# USBDM_Kinetis.net
KiCad netlist of a schematic drawn in Altium Designer
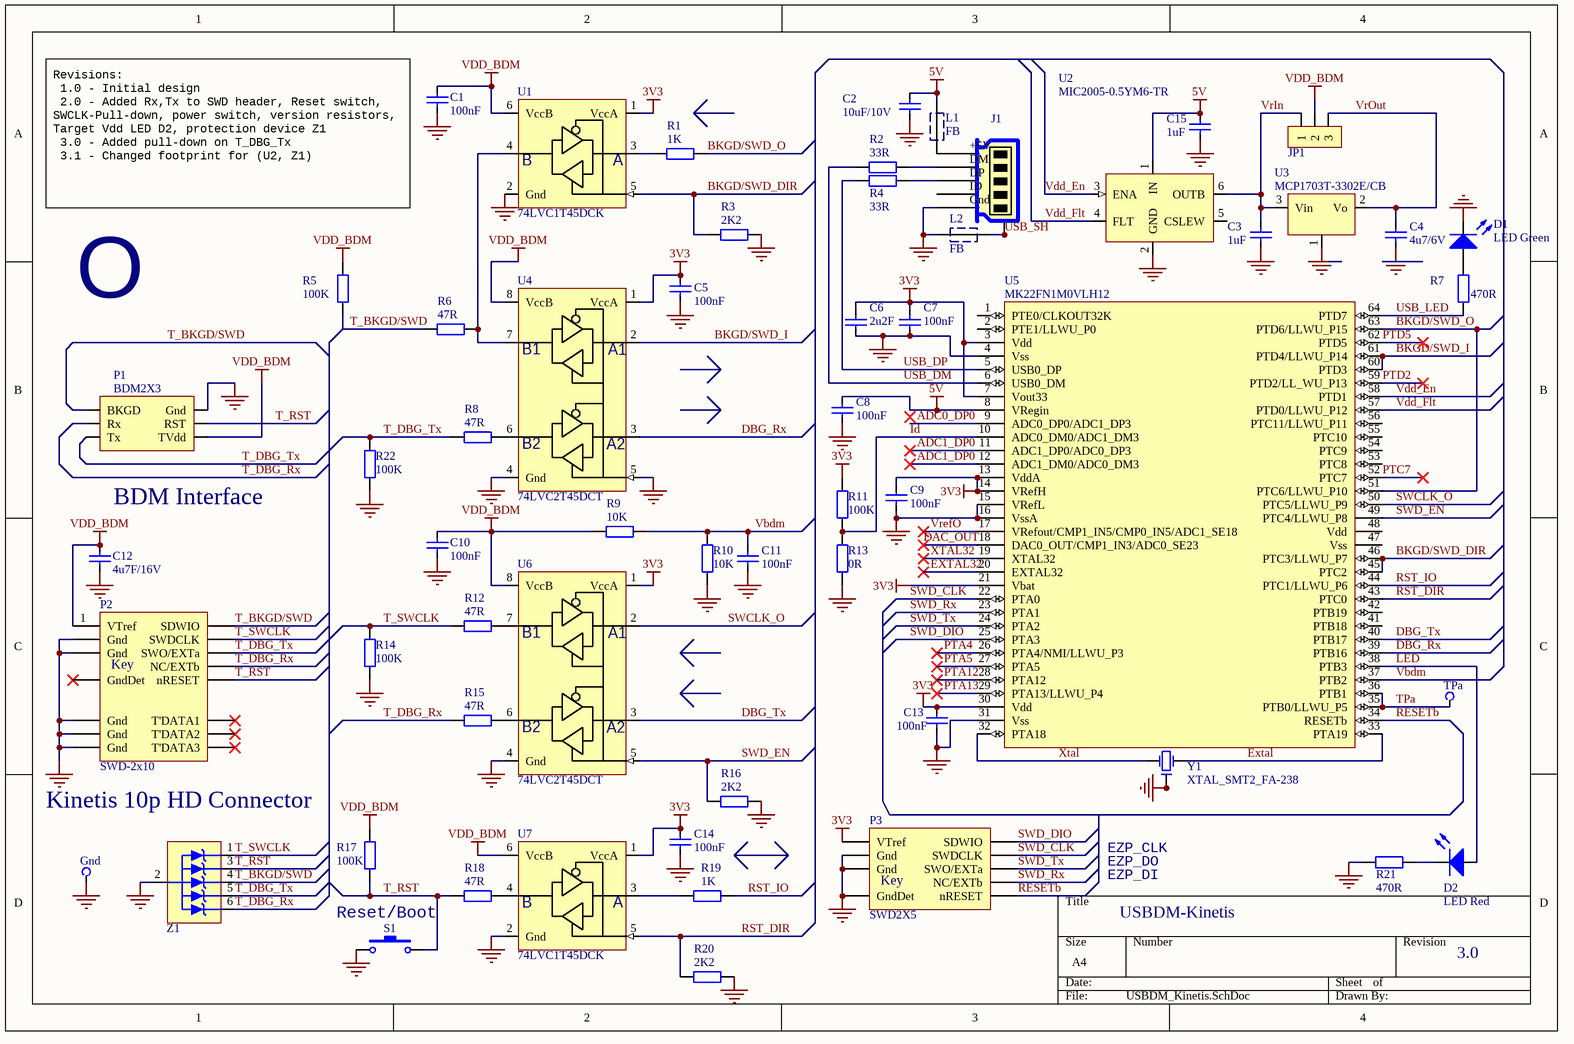
[diagram p0: USBDM_Kinetis.SchDoc]

(export (version "E")
  (design (tool "Eeschema 10.0.6"))
  (components
    (comp (ref "C1")
      (value "100nF")
      (footprint "CCNP1608-0603")
      (description "Capacitor")
      (fields
        (field (name "MANUFACTURER") "Generic Components")
        (field (name "PUBLISHER") "Altium Hobart Technology Centre")
      )
      (libsource (lib "MyLibrary") (part "Cap_CCNP_0603"))
    )
    (comp (ref "C2")
      (value "10uF/10V")
      (footprint "CCNP2012-0805")
      (description "Capacitor SMT 0805")
      (fields
        (field (name "MANUFACTURER") "Generic Components")
        (field (name "PUBLISHER") "Altium Hobart Technology Centre")
      )
      (libsource (lib "MyLibrary") (part "Cap_CCNP_0805"))
    )
    (comp (ref "C3")
      (value "1uF")
      (footprint "CCNP1608-0603")
      (description "Capacitor SMT")
      (fields
        (field (name "MANUFACTURER") "Generic Components")
        (field (name "PUBLISHER") "Altium Hobart Technology Centre")
      )
      (libsource (lib "MyLibrary") (part "Cap"))
    )
    (comp (ref "C4")
      (value "4u7/6V")
      (footprint "CCNP1608-0603")
      (description "Capacitor SMT 0603")
      (fields
        (field (name "MANUFACTURER") "Generic Components")
        (field (name "PUBLISHER") "Altium Hobart Technology Centre")
      )
      (libsource (lib "MyLibrary") (part "Cap_CCNP_0603"))
    )
    (comp (ref "C5")
      (value "100nF")
      (footprint "CCNP1608-0603")
      (description "Capacitor")
      (fields
        (field (name "MANUFACTURER") "Generic Components")
        (field (name "PUBLISHER") "Altium Hobart Technology Centre")
      )
      (libsource (lib "MyLibrary") (part "Cap_CCNP_0603"))
    )
    (comp (ref "C6")
      (value "2u2F")
      (footprint "CCNP1608-0603")
      (description "Capacitor SMT 0603")
      (fields
        (field (name "MANUFACTURER") "Generic Components")
        (field (name "PUBLISHER") "Altium Hobart Technology Centre")
      )
      (libsource (lib "MyLibrary") (part "Cap_CCNP_0603"))
    )
    (comp (ref "C7")
      (value "100nF")
      (footprint "CCNP1608-0603")
      (description "Capacitor")
      (fields
        (field (name "MANUFACTURER") "Generic Components")
        (field (name "PUBLISHER") "Altium Hobart Technology Centre")
      )
      (libsource (lib "MyLibrary") (part "Cap_CCNP_0603"))
    )
    (comp (ref "C8")
      (value "100nF")
      (footprint "CCNP1608-0603")
      (description "Capacitor")
      (fields
        (field (name "MANUFACTURER") "Generic Components")
        (field (name "PUBLISHER") "Altium Hobart Technology Centre")
      )
      (libsource (lib "MyLibrary") (part "Cap_CCNP_0603"))
    )
    (comp (ref "C9")
      (value "100nF")
      (footprint "CCNP1608-0603")
      (description "Capacitor")
      (fields
        (field (name "MANUFACTURER") "Generic Components")
        (field (name "PUBLISHER") "Altium Hobart Technology Centre")
      )
      (libsource (lib "MyLibrary") (part "Cap_CCNP_0603"))
    )
    (comp (ref "C10")
      (value "100nF")
      (footprint "CCNP1608-0603")
      (description "Capacitor")
      (fields
        (field (name "MANUFACTURER") "Generic Components")
        (field (name "PUBLISHER") "Altium Hobart Technology Centre")
      )
      (libsource (lib "MyLibrary") (part "Cap_CCNP_0603"))
    )
    (comp (ref "C11")
      (value "100nF")
      (footprint "CCNP1608-0603")
      (description "Capacitor")
      (fields
        (field (name "MANUFACTURER") "Generic Components")
        (field (name "PUBLISHER") "Altium Hobart Technology Centre")
      )
      (libsource (lib "MyLibrary") (part "Cap_CCNP_0603"))
    )
    (comp (ref "C12")
      (value "4u7F/16V")
      (footprint "CCNP2012-0805")
      (description "Capacitor SMT 0805")
      (fields
        (field (name "MANUFACTURER") "Generic Components")
        (field (name "PUBLISHER") "Altium Hobart Technology Centre")
      )
      (libsource (lib "MyLibrary") (part "Cap_CCNP_0805"))
    )
    (comp (ref "C13")
      (value "100nF")
      (footprint "CCNP1608-0603")
      (description "Capacitor")
      (fields
        (field (name "MANUFACTURER") "Generic Components")
        (field (name "PUBLISHER") "Altium Hobart Technology Centre")
      )
      (libsource (lib "MyLibrary") (part "Cap_CCNP_0603"))
    )
    (comp (ref "C14")
      (value "100nF")
      (footprint "CCNP1608-0603")
      (description "Capacitor")
      (fields
        (field (name "MANUFACTURER") "Generic Components")
        (field (name "PUBLISHER") "Altium Hobart Technology Centre")
      )
      (libsource (lib "MyLibrary") (part "Cap_CCNP_0603"))
    )
    (comp (ref "C15")
      (value "1uF")
      (footprint "CCNP1608-0603")
      (description "Capacitor SMT")
      (fields
        (field (name "MANUFACTURER") "Generic Components")
        (field (name "PUBLISHER") "Altium Hobart Technology Centre")
      )
      (libsource (lib "MyLibrary") (part "Cap"))
    )
    (comp (ref "D1")
      (value "LED Green")
      (footprint "CD1608-0603")
      (description "LED (Red 0603)")
      (fields (field (name "MANUFACTURER") "Generic Components") (field (name "PUBLISHER") "Altium Limited"))
      (libsource (lib "MySchLib") (part "LED SMT,Red-0603"))
    )
    (comp (ref "D2")
      (value "LED Red")
      (footprint "CD1608-0603")
      (description "LED (Red 0603)")
      (fields (field (name "MANUFACTURER") "Generic Components") (field (name "PUBLISHER") "Altium Limited"))
      (libsource (lib "MySchLib") (part "LED SMT,Red-0603"))
    )
    (comp (ref "Gnd")
      (value "TP")
      (footprint "PCBPIN - 0.9mm")
      (description "Test Point")
      (libsource (lib "MyLibrary") (part "TP"))
    )
    (comp (ref "J1")
      (value "USB_MICRO_B_CONNECTOR")
      (footprint "MOLEX - 47346-0001")
      (description "USB Micro-B Connector")
      (libsource (lib "MySchLib") (part "USB_MICRO_B_CONNECTOR"))
    )
    (comp (ref "JP1")
      (value "Header 1x3 2mm")
      (footprint "Header 1x3 (2mm)")
      (description "Header, 1x3, 2mm")
      (fields (field (name "MANUFACTURER") "Generic Components") (field (name "PUBLISHER") "Altium Limited"))
      (libsource (lib "MySchLib") (part "Header 1x3 2mm"))
    )
    (comp (ref "L1")
      (value "FB")
      (footprint "CR2012-0805")
      (description "Ferrite Bead (0805) 0.045OHM, 2A")
      (libsource (lib "MySchLib") (part "Ferrite Bead 0805"))
    )
    (comp (ref "L2")
      (value "FB")
      (footprint "CR2012-0805")
      (description "Ferrite Bead (0805) 0.045OHM, 2A")
      (libsource (lib "MySchLib") (part "Ferrite Bead 0805"))
    )
    (comp (ref "Logo1")
      (value "OSHW Logo")
      (footprint "OSHW")
      (libsource (lib "MySchLib") (part "OSHW Logo"))
    )
    (comp (ref "P1") (value "BDM2X3") (footprint "BDM") (libsource (lib "MyLibrary") (part "BDM2X3")))
    (comp (ref "P2")
      (value "SWD-2x10")
      (footprint "SWD-2x10 - reduced")
      (description "SWD Connector 2x10-Pin")
      (fields (field (name "PUBLISHER") "Altium Limited"))
      (libsource (lib "MySchLib") (part "SWD2X10-Reduced"))
    )
    (comp (ref "P3")
      (value "SWD2X5")
      (footprint "SWD-2x5")
      (description "SWD Connector 2x5-Pin")
      (fields (field (name "PUBLISHER") "Altium Limited"))
      (libsource (lib "MySchLib") (part "SWD2X5"))
    )
    (comp (ref "R1")
      (value "1K")
      (footprint "CR1608-0603")
      (description "Resistor SMT")
      (fields
        (field (name "MANUFACTURER") "Generic Components")
        (field (name "PUBLISHER") "Altium Hobart Technology Centre")
      )
      (libsource (lib "") (part "Res_CR0603_3"))
    )
    (comp (ref "R2")
      (value "33R")
      (footprint "CR1608-0603")
      (description "Resistor")
      (fields
        (field (name "MANUFACTURER") "Generic Components")
        (field (name "PUBLISHER") "Altium Hobart Technology Centre")
      )
      (libsource (lib "MyLibrary") (part "Res_CR0603"))
    )
    (comp (ref "R3")
      (value "2K2")
      (footprint "CR1608-0603")
      (description "Resistor SMT")
      (fields
        (field (name "MANUFACTURER") "Generic Components")
        (field (name "PUBLISHER") "Altium Hobart Technology Centre")
      )
      (libsource (lib "") (part "Res_CR0603_5"))
    )
    (comp (ref "R4")
      (value "33R")
      (footprint "CR1608-0603")
      (description "Resistor")
      (fields
        (field (name "MANUFACTURER") "Generic Components")
        (field (name "PUBLISHER") "Altium Hobart Technology Centre")
      )
      (libsource (lib "MyLibrary") (part "Res_CR0603"))
    )
    (comp (ref "R5")
      (value "100K")
      (footprint "CR1608-0603")
      (description "Resistor SMT")
      (fields
        (field (name "MANUFACTURER") "Generic Components")
        (field (name "PUBLISHER") "Altium Hobart Technology Centre")
      )
      (libsource (lib "") (part "Res_CR0603_4"))
    )
    (comp (ref "R6")
      (value "47R")
      (footprint "CR1608-0603")
      (description "Resistor SMT")
      (fields
        (field (name "MANUFACTURER") "Generic Components")
        (field (name "PUBLISHER") "Altium Hobart Technology Centre")
      )
      (libsource (lib "") (part "Res_CR0603_2"))
    )
    (comp (ref "R7")
      (value "470R")
      (footprint "CR1608-0603")
      (description "Resistor SMT")
      (fields
        (field (name "MANUFACTURER") "Generic Components")
        (field (name "PUBLISHER") "Altium Hobart Technology Centre")
      )
      (libsource (lib "") (part "Res_CR0603_3"))
    )
    (comp (ref "R8")
      (value "47R")
      (footprint "CR1608-0603")
      (description "Resistor SMT")
      (fields
        (field (name "MANUFACTURER") "Generic Components")
        (field (name "PUBLISHER") "Altium Hobart Technology Centre")
      )
      (libsource (lib "") (part "Res_CR0603_2"))
    )
    (comp (ref "R9")
      (value "10K")
      (footprint "CR1608-0603")
      (description "Resistor SMT")
      (fields
        (field (name "MANUFACTURER") "Generic Components")
        (field (name "PUBLISHER") "Altium Hobart Technology Centre")
      )
      (libsource (lib "") (part "Res_CR0603_2"))
    )
    (comp (ref "R10")
      (value "10K")
      (footprint "CR1608-0603")
      (description "Resistor SMT")
      (fields
        (field (name "MANUFACTURER") "Generic Components")
        (field (name "PUBLISHER") "Altium Hobart Technology Centre")
      )
      (libsource (lib "") (part "Res_CR0603_3"))
    )
    (comp (ref "R11")
      (value "100K")
      (footprint "CR1608-0603")
      (description "Resistor")
      (fields
        (field (name "MANUFACTURER") "Generic Components")
        (field (name "PUBLISHER") "Altium Hobart Technology Centre")
      )
      (libsource (lib "") (part "Res_CR0603_6"))
    )
    (comp (ref "R12")
      (value "47R")
      (footprint "CR1608-0603")
      (description "Resistor SMT")
      (fields
        (field (name "MANUFACTURER") "Generic Components")
        (field (name "PUBLISHER") "Altium Hobart Technology Centre")
      )
      (libsource (lib "") (part "Res_CR0603_2"))
    )
    (comp (ref "R13")
      (value "0R")
      (footprint "CR1608-0603")
      (description "Resistor")
      (fields
        (field (name "MANUFACTURER") "Generic Components")
        (field (name "PUBLISHER") "Altium Hobart Technology Centre")
      )
      (libsource (lib "") (part "Res_CR0603_6"))
    )
    (comp (ref "R14")
      (value "100K")
      (footprint "CR1608-0603")
      (description "Resistor SMT")
      (fields
        (field (name "MANUFACTURER") "Generic Components")
        (field (name "PUBLISHER") "Altium Hobart Technology Centre")
      )
      (libsource (lib "") (part "Res_CR0603_1"))
    )
    (comp (ref "R15")
      (value "47R")
      (footprint "CR1608-0603")
      (description "Resistor SMT")
      (fields
        (field (name "MANUFACTURER") "Generic Components")
        (field (name "PUBLISHER") "Altium Hobart Technology Centre")
      )
      (libsource (lib "") (part "Res_CR0603_2"))
    )
    (comp (ref "R16")
      (value "2K2")
      (footprint "CR1608-0603")
      (description "Resistor SMT")
      (fields
        (field (name "MANUFACTURER") "Generic Components")
        (field (name "PUBLISHER") "Altium Hobart Technology Centre")
      )
      (libsource (lib "") (part "Res_CR0603_7"))
    )
    (comp (ref "R17")
      (value "100K")
      (footprint "CR1608-0603")
      (description "Resistor SMT")
      (fields
        (field (name "MANUFACTURER") "Generic Components")
        (field (name "PUBLISHER") "Altium Hobart Technology Centre")
      )
      (libsource (lib "") (part "Res_CR0603_4"))
    )
    (comp (ref "R18")
      (value "47R")
      (footprint "CR1608-0603")
      (description "Resistor SMT")
      (fields
        (field (name "MANUFACTURER") "Generic Components")
        (field (name "PUBLISHER") "Altium Hobart Technology Centre")
      )
      (libsource (lib "") (part "Res_CR0603_2"))
    )
    (comp (ref "R19")
      (value "1K")
      (footprint "CR1608-0603")
      (description "Resistor SMT")
      (fields
        (field (name "MANUFACTURER") "Generic Components")
        (field (name "PUBLISHER") "Altium Hobart Technology Centre")
      )
      (libsource (lib "") (part "Res_CR0603_2"))
    )
    (comp (ref "R20")
      (value "2K2")
      (footprint "CR1608-0603")
      (description "Resistor SMT")
      (fields
        (field (name "MANUFACTURER") "Generic Components")
        (field (name "PUBLISHER") "Altium Hobart Technology Centre")
      )
      (libsource (lib "") (part "Res_CR0603_5"))
    )
    (comp (ref "R21")
      (value "470R")
      (footprint "CR1608-0603")
      (description "Resistor SMT")
      (fields
        (field (name "MANUFACTURER") "Generic Components")
        (field (name "PUBLISHER") "Altium Hobart Technology Centre")
      )
      (libsource (lib "") (part "Res_CR0603_5"))
    )
    (comp (ref "R22")
      (value "100K")
      (footprint "CR1608-0603")
      (description "Resistor SMT")
      (fields
        (field (name "MANUFACTURER") "Generic Components")
        (field (name "PUBLISHER") "Altium Hobart Technology Centre")
      )
      (libsource (lib "") (part "Res_CR0603_1"))
    )
    (comp (ref "S1")
      (value "SW-PB-SMT-B3U")
      (footprint "SW_SMT_PB2-B3U")
      (description "Switch OMRON B3U series")
      (fields (field (name "MANUFACTURER") "Generic Components") (field (name "PUBLISHER") "Altium Limited"))
      (libsource (lib "MyLibrary") (part "SW-PB-SMT-B3U"))
    )
    (comp (ref "TPa")
      (value "TP")
      (footprint "PCBPIN - 0.9mm")
      (description "Test Point")
      (libsource (lib "MyLibrary") (part "TP"))
    )
    (comp (ref "U1")
      (value "74LVC1T45DCK")
      (footprint "SC70_N")
      (description "Dual voltage bidirection buffer")
      (libsource (lib "MySchLib") (part "74LVC1T45DCK"))
    )
    (comp (ref "U2")
      (value "MIC2005-0.5YM6-TR")
      (footprint "SOT23-6-Power")
      (description "Power Switch")
      (libsource (lib "MySchLib") (part "MIC2005-0.5YM6-TR"))
    )
    (comp (ref "U3")
      (value "MCP1703T-3302E/CB")
      (footprint "SOT23")
      (description "3V3 LDO regulator")
      (libsource (lib "MyLibrary") (part "MCP1703T-3302E/CB"))
    )
    (comp (ref "U4")
      (value "74LVC2T45DCT")
      (footprint "SSOP8_N")
      (description "Dual voltage bidirection buffer")
      (libsource (lib "MySchLib") (part "74LVC2T45DCT"))
    )
    (comp (ref "U5")
      (value "MK22FN1M0VLH12")
      (footprint "TSQFP50P1200X1200-64N")
      (description "Arm Cortex M4F")
      (libsource (lib "MyLibrary") (part "MK22FN1M0VLH12"))
    )
    (comp (ref "U6")
      (value "74LVC2T45DCT")
      (footprint "SSOP8_N")
      (description "Dual voltage bidirection buffer")
      (libsource (lib "MySchLib") (part "74LVC2T45DCT"))
    )
    (comp (ref "U7")
      (value "74LVC1T45DCK")
      (footprint "SC70_N")
      (description "Dual voltage bidirection buffer")
      (libsource (lib "MySchLib") (part "74LVC1T45DCK"))
    )
    (comp (ref "Y1")
      (value "XTAL_SMT2_FA-238")
      (footprint "Crystal_SMT - EPSON-FA-238")
      (description "Crystal (EPSON  Q22FA23800065 FA-238 24 MHZ 12.0PF)")
      (fields
        (field (name "MANUFACTURER") "Generic Components")
        (field (name "PUBLISHER") "Altium Hobart Technology Centre")
      )
      (libsource (lib "MyLibrary") (part "XTAL_SMT2_FA-238"))
    )
    (comp (ref "Z1")
      (value "82402305")
      (footprint "SOT23-6")
      (description "Quintuple Unipolar Protection Device (5V)")
      (libsource (lib "MySchLib") (part "82402305"))
    )
  )
  (nets
    (net (code "1") (name "/ADC0_DP0") (class "Default")
      (node (ref "U5") (pin "9") (pinfunction "ADC0_DP0/ADC1_DP3_9") (pintype "passive"))
    )
    (net (code "2") (name "/ADC1_DP0") (class "Default")
      (node (ref "U5") (pin "11") (pinfunction "ADC1_DP0/ADC0_DP3_11") (pintype "passive"))
      (node (ref "U5") (pin "12") (pinfunction "ADC1_DM0/ADC0_DM3_12") (pintype "passive"))
    )
    (net (code "3") (name "/BKGD{slash}SWD_DIR") (class "Default")
      (node (ref "R3") (pin "1") (pinfunction "1_1") (pintype "passive"))
      (node (ref "U1") (pin "5") (pinfunction "DIR_5") (pintype "input"))
      (node (ref "U5") (pin "45") (pinfunction "PTC2_45") (pintype "bidirectional"))
      (node (ref "U5") (pin "46") (pinfunction "PTC3/LLWU_P7_46") (pintype "bidirectional"))
    )
    (net (code "4") (name "/BKGD{slash}SWD_I") (class "Default")
      (node (ref "U4") (pin "2") (pinfunction "A1_2") (pintype "bidirectional"))
      (node (ref "U5") (pin "60") (pinfunction "PTD3_60") (pintype "bidirectional"))
      (node (ref "U5") (pin "61") (pinfunction "PTD4/LLWU_P14_61") (pintype "bidirectional"))
    )
    (net (code "5") (name "/BKGD{slash}SWD_O") (class "Default")
      (node (ref "R1") (pin "1") (pinfunction "1_1") (pintype "passive"))
      (node (ref "U5") (pin "51") (pinfunction "PTC6/LLWU_P10_51") (pintype "bidirectional"))
      (node (ref "U5") (pin "63") (pinfunction "PTD6/LLWU_P15_63") (pintype "bidirectional"))
    )
    (net (code "6") (name "/DAC_OUT") (class "Default")
      (node (ref "U5") (pin "18") (pinfunction "DAC0_OUT/CMP1_IN3/ADC0_SE23_18") (pintype "passive+no_connect"))
    )
    (net (code "7") (name "/DBG_Rx") (class "Default")
      (node (ref "U4") (pin "3") (pinfunction "A2_3") (pintype "bidirectional"))
      (node (ref "U5") (pin "39") (pinfunction "PTB16_39") (pintype "bidirectional"))
    )
    (net (code "8") (name "/DBG_Tx") (class "Default")
      (node (ref "U5") (pin "40") (pinfunction "PTB17_40") (pintype "bidirectional"))
      (node (ref "U6") (pin "3") (pinfunction "A2_3") (pintype "bidirectional"))
    )
    (net (code "9") (name "/EXTAL32") (class "Default")
      (node (ref "U5") (pin "20") (pinfunction "EXTAL32_20") (pintype "passive+no_connect"))
    )
    (net (code "10") (name "/Extal") (class "Default")
      (node (ref "U5") (pin "33") (pinfunction "PTA19_33") (pintype "bidirectional"))
      (node (ref "Y1") (pin "3") (pinfunction "OSC2_3") (pintype "passive"))
    )
    (net (code "11") (name "/Id") (class "Default")
      (node (ref "R11") (pin "1") (pinfunction "1_1") (pintype "passive"))
      (node (ref "R13") (pin "2") (pinfunction "2_2") (pintype "passive"))
      (node (ref "U5") (pin "10") (pinfunction "ADC0_DM0/ADC1_DM3_10") (pintype "passive"))
    )
    (net (code "12") (name "/LED") (class "Default")
      (node (ref "D2") (pin "A") (pinfunction "A_A") (pintype "passive"))
      (node (ref "U5") (pin "38") (pinfunction "PTB3_38") (pintype "bidirectional"))
    )
    (net (code "13") (name "/PTA4") (class "Default")
      (node (ref "U5") (pin "26") (pinfunction "PTA4/NMI/LLWU_P3_26") (pintype "bidirectional+no_connect"))
    )
    (net (code "14") (name "/PTA5") (class "Default")
      (node (ref "U5") (pin "27") (pinfunction "PTA5_27") (pintype "bidirectional+no_connect"))
    )
    (net (code "15") (name "/PTA12") (class "Default")
      (node (ref "U5") (pin "28") (pinfunction "PTA12_28") (pintype "bidirectional+no_connect"))
    )
    (net (code "16") (name "/PTA13") (class "Default")
      (node (ref "U5") (pin "29") (pinfunction "PTA13/LLWU_P4_29") (pintype "bidirectional+no_connect"))
    )
    (net (code "17") (name "/PTC7") (class "Default")
      (node (ref "U5") (pin "52") (pinfunction "PTC7_52") (pintype "bidirectional+no_connect"))
    )
    (net (code "18") (name "/PTD2") (class "Default")
      (node (ref "U5") (pin "59") (pinfunction "PTD2/LL_WU_P13_59") (pintype "bidirectional+no_connect"))
    )
    (net (code "19") (name "/PTD5") (class "Default")
      (node (ref "U5") (pin "62") (pinfunction "PTD5_62") (pintype "bidirectional+no_connect"))
    )
    (net (code "20") (name "/RESETb") (class "Default")
      (node (ref "P3") (pin "10") (pinfunction "nRESET_10") (pintype "passive"))
      (node (ref "U5") (pin "34") (pinfunction "RESETb_34") (pintype "bidirectional"))
    )
    (net (code "21") (name "/RST_DIR") (class "Default")
      (node (ref "R20") (pin "1") (pinfunction "1_1") (pintype "passive"))
      (node (ref "U5") (pin "43") (pinfunction "PTC0_43") (pintype "bidirectional"))
      (node (ref "U7") (pin "5") (pinfunction "DIR_5") (pintype "input"))
    )
    (net (code "22") (name "/RST_IO") (class "Default")
      (node (ref "R19") (pin "1") (pinfunction "1_1") (pintype "passive"))
      (node (ref "U5") (pin "44") (pinfunction "PTC1/LLWU_P6_44") (pintype "bidirectional"))
    )
    (net (code "23") (name "/SWCLK_O") (class "Default")
      (node (ref "U5") (pin "50") (pinfunction "PTC5/LLWU_P9_50") (pintype "bidirectional"))
      (node (ref "U6") (pin "2") (pinfunction "A1_2") (pintype "bidirectional"))
    )
    (net (code "24") (name "/SWD_CLK") (class "Default")
      (node (ref "P3") (pin "4") (pinfunction "SWDCLK_4") (pintype "passive"))
      (node (ref "U5") (pin "22") (pinfunction "PTA0_22") (pintype "bidirectional"))
    )
    (net (code "25") (name "/SWD_DIO") (class "Default")
      (node (ref "P3") (pin "2") (pinfunction "SDWIO_2") (pintype "passive"))
      (node (ref "U5") (pin "25") (pinfunction "PTA3_25") (pintype "bidirectional"))
    )
    (net (code "26") (name "/SWD_EN") (class "Default")
      (node (ref "R16") (pin "1") (pinfunction "1_1") (pintype "passive"))
      (node (ref "U5") (pin "49") (pinfunction "PTC4/LLWU_P8_49") (pintype "power_in"))
      (node (ref "U6") (pin "5") (pinfunction "DIR_5") (pintype "input"))
    )
    (net (code "27") (name "/SWD_Rx") (class "Default")
      (node (ref "P3") (pin "8") (pinfunction "NC/EXTb_8") (pintype "passive"))
      (node (ref "U5") (pin "23") (pinfunction "PTA1_23") (pintype "bidirectional"))
    )
    (net (code "28") (name "/SWD_Tx") (class "Default")
      (node (ref "P3") (pin "6") (pinfunction "SWO/EXTa_6") (pintype "passive"))
      (node (ref "U5") (pin "24") (pinfunction "PTA2_24") (pintype "bidirectional"))
    )
    (net (code "29") (name "/TPa") (class "Default")
      (node (ref "TPa") (pin "1") (pinfunction "TP_1") (pintype "passive"))
      (node (ref "U5") (pin "35") (pinfunction "PTB0/LLWU_P5_35") (pintype "bidirectional"))
      (node (ref "U5") (pin "36") (pinfunction "PTB1_36") (pintype "bidirectional"))
    )
    (net (code "30") (name "/T_BKGD{slash}SWD") (class "Default")
      (node (ref "P1") (pin "1") (pinfunction "BKGD_1") (pintype "passive"))
      (node (ref "P2") (pin "2") (pinfunction "SDWIO_2") (pintype "passive"))
      (node (ref "R5") (pin "2") (pinfunction "2_2") (pintype "passive"))
      (node (ref "R6") (pin "2") (pinfunction "2_2") (pintype "passive"))
      (node (ref "Z1") (pin "4") (pintype "passive"))
    )
    (net (code "31") (name "/T_DBG_Rx") (class "Default")
      (node (ref "P1") (pin "3") (pinfunction "Rx_3") (pintype "passive"))
      (node (ref "P2") (pin "8") (pinfunction "NC/EXTb_8") (pintype "passive"))
      (node (ref "R15") (pin "2") (pinfunction "2_2") (pintype "passive"))
      (node (ref "Z1") (pin "6") (pintype "passive"))
    )
    (net (code "32") (name "/T_DBG_Tx") (class "Default")
      (node (ref "P1") (pin "5") (pinfunction "Tx_5") (pintype "passive"))
      (node (ref "P2") (pin "6") (pinfunction "SWO/EXTa_6") (pintype "passive"))
      (node (ref "R22") (pin "2") (pinfunction "2_2") (pintype "passive"))
      (node (ref "R8") (pin "2") (pinfunction "2_2") (pintype "passive"))
      (node (ref "Z1") (pin "5") (pintype "passive"))
    )
    (net (code "33") (name "/T_RST") (class "Default")
      (node (ref "P1") (pin "4") (pinfunction "RST_4") (pintype "passive"))
      (node (ref "P2") (pin "10") (pinfunction "nRESET_10") (pintype "passive"))
      (node (ref "R17") (pin "2") (pinfunction "2_2") (pintype "passive"))
      (node (ref "R18") (pin "2") (pinfunction "2_2") (pintype "passive"))
      (node (ref "S1") (pin "2") (pinfunction "2_2") (pintype "passive"))
      (node (ref "Z1") (pin "3") (pintype "passive"))
    )
    (net (code "34") (name "/T_SWCLK") (class "Default")
      (node (ref "P2") (pin "4") (pinfunction "SWDCLK_4") (pintype "passive"))
      (node (ref "R12") (pin "2") (pinfunction "2_2") (pintype "passive"))
      (node (ref "R14") (pin "2") (pinfunction "2_2") (pintype "passive"))
      (node (ref "Z1") (pin "1") (pintype "passive"))
    )
    (net (code "35") (name "/USB_DM") (class "Default")
      (node (ref "R2") (pin "2") (pinfunction "2_2") (pintype "passive"))
      (node (ref "U5") (pin "6") (pinfunction "USB0_DM_6") (pintype "bidirectional"))
    )
    (net (code "36") (name "/USB_DP") (class "Default")
      (node (ref "R4") (pin "2") (pinfunction "2_2") (pintype "passive"))
      (node (ref "U5") (pin "5") (pinfunction "USB0_DP_5") (pintype "bidirectional"))
    )
    (net (code "37") (name "/USB_LED") (class "Default")
      (node (ref "R7") (pin "2") (pinfunction "2_2") (pintype "passive"))
      (node (ref "U5") (pin "64") (pinfunction "PTD7_64") (pintype "bidirectional"))
    )
    (net (code "38") (name "/USB_SH") (class "Default")
      (node (ref "J1") (pin "S1") (pinfunction "USBShd_S1") (pintype "passive"))
      (node (ref "J1") (pin "S2") (pinfunction "USBShd_S2") (pintype "passive"))
      (node (ref "J1") (pin "S3") (pinfunction "USBShd_S3") (pintype "passive"))
      (node (ref "J1") (pin "S4") (pinfunction "USBShd_S4") (pintype "passive"))
      (node (ref "J1") (pin "S5") (pinfunction "USBShd_S5") (pintype "passive"))
      (node (ref "J1") (pin "S6") (pinfunction "USBShd_S6") (pintype "passive"))
      (node (ref "L2") (pin "1") (pinfunction "1_1") (pintype "passive"))
    )
    (net (code "39") (name "/Vbdm") (class "Default")
      (node (ref "C11") (pin "2") (pinfunction "2_2") (pintype "passive"))
      (node (ref "R10") (pin "1") (pinfunction "1_1") (pintype "passive"))
      (node (ref "R9") (pin "1") (pinfunction "1_1") (pintype "passive"))
      (node (ref "U5") (pin "37") (pinfunction "PTB2_37") (pintype "bidirectional"))
    )
    (net (code "40") (name "/Vdd_En") (class "Default")
      (node (ref "U2") (pin "3") (pinfunction "ENA_3") (pintype "input"))
      (node (ref "U5") (pin "58") (pinfunction "PTD1_58") (pintype "bidirectional"))
    )
    (net (code "41") (name "/Vdd_Flt") (class "Default")
      (node (ref "U2") (pin "4") (pinfunction "FLT_4") (pintype "open_collector"))
      (node (ref "U5") (pin "57") (pinfunction "PTD0/LLWU_P12_57") (pintype "bidirectional"))
    )
    (net (code "42") (name "/VrIn") (class "Default")
      (node (ref "C3") (pin "2") (pinfunction "2_2") (pintype "passive"))
      (node (ref "JP1") (pin "1") (pinfunction "1_1") (pintype "passive"))
      (node (ref "U2") (pin "6") (pinfunction "OUTB_6") (pintype "passive"))
      (node (ref "U3") (pin "3") (pinfunction "Vin_3") (pintype "passive"))
    )
    (net (code "43") (name "/VrOut") (class "Default")
      (node (ref "C4") (pin "2") (pinfunction "2_2") (pintype "passive"))
      (node (ref "JP1") (pin "3") (pinfunction "3_3") (pintype "passive"))
      (node (ref "U3") (pin "2") (pinfunction "Vo_2") (pintype "passive"))
    )
    (net (code "44") (name "/VrefO") (class "Default")
      (node (ref "U5") (pin "17") (pinfunction "VRefout/CMP1_IN5/CMP0_IN5/ADC1_SE18_17") (pintype "passive+no_connect"))
    )
    (net (code "45") (name "/XTAL32") (class "Default")
      (node (ref "U5") (pin "19") (pinfunction "XTAL32_19") (pintype "passive+no_connect"))
    )
    (net (code "46") (name "/Xtal") (class "Default")
      (node (ref "U5") (pin "32") (pinfunction "PTA18_32") (pintype "bidirectional"))
      (node (ref "Y1") (pin "1") (pinfunction "OSC1_1") (pintype "passive"))
    )
    (net (code "47") (name "3V3") (class "Default")
      (node (ref "C13") (pin "2") (pinfunction "2_2") (pintype "passive"))
      (node (ref "C14") (pin "2") (pinfunction "2_2") (pintype "passive"))
      (node (ref "C5") (pin "2") (pinfunction "2_2") (pintype "passive"))
      (node (ref "C6") (pin "2") (pinfunction "2_2") (pintype "passive"))
      (node (ref "C7") (pin "2") (pinfunction "2_2") (pintype "passive"))
      (node (ref "C9") (pin "2") (pinfunction "2_2") (pintype "passive"))
      (node (ref "P3") (pin "1") (pinfunction "VTref_1") (pintype "passive"))
      (node (ref "R11") (pin "2") (pinfunction "2_2") (pintype "passive"))
      (node (ref "U1") (pin "1") (pinfunction "VccA_1") (pintype "power_in"))
      (node (ref "U4") (pin "1") (pinfunction "VccA_1") (pintype "power_in"))
      (node (ref "U5") (pin "13") (pinfunction "VddA_13") (pintype "power_in"))
      (node (ref "U5") (pin "14") (pinfunction "VRefH_14") (pintype "passive"))
      (node (ref "U5") (pin "21") (pinfunction "Vbat_21") (pintype "passive"))
      (node (ref "U5") (pin "3") (pinfunction "Vdd_3") (pintype "power_in"))
      (node (ref "U5") (pin "30") (pinfunction "Vdd_30") (pintype "power_in"))
      (node (ref "U5") (pin "7") (pinfunction "Vout33_7") (pintype "power_in"))
      (node (ref "U6") (pin "1") (pinfunction "VccA_1") (pintype "power_in"))
      (node (ref "U7") (pin "1") (pinfunction "VccA_1") (pintype "power_in"))
    )
    (net (code "48") (name "5V") (class "Default")
      (node (ref "C15") (pin "2") (pinfunction "2_2") (pintype "passive"))
      (node (ref "C2") (pin "2") (pinfunction "2_2") (pintype "passive"))
      (node (ref "C8") (pin "2") (pinfunction "2_2") (pintype "passive"))
      (node (ref "L1") (pin "2") (pinfunction "2_2") (pintype "passive"))
      (node (ref "U2") (pin "1") (pinfunction "IN_1") (pintype "passive"))
      (node (ref "U5") (pin "8") (pinfunction "VRegin_8") (pintype "passive"))
    )
    (net (code "49") (name "GND") (class "Default")
      (node (ref "C1") (pin "1") (pinfunction "1_1") (pintype "passive"))
      (node (ref "C10") (pin "1") (pinfunction "1_1") (pintype "passive"))
      (node (ref "C11") (pin "1") (pinfunction "1_1") (pintype "passive"))
      (node (ref "C12") (pin "1") (pinfunction "1_1") (pintype "passive"))
      (node (ref "C13") (pin "1") (pinfunction "1_1") (pintype "passive"))
      (node (ref "C14") (pin "1") (pinfunction "1_1") (pintype "passive"))
      (node (ref "C15") (pin "1") (pinfunction "1_1") (pintype "passive"))
      (node (ref "C2") (pin "1") (pinfunction "1_1") (pintype "passive"))
      (node (ref "C3") (pin "1") (pinfunction "1_1") (pintype "passive"))
      (node (ref "C4") (pin "1") (pinfunction "1_1") (pintype "passive"))
      (node (ref "C5") (pin "1") (pinfunction "1_1") (pintype "passive"))
      (node (ref "C6") (pin "1") (pinfunction "1_1") (pintype "passive"))
      (node (ref "C7") (pin "1") (pinfunction "1_1") (pintype "passive"))
      (node (ref "C8") (pin "1") (pinfunction "1_1") (pintype "passive"))
      (node (ref "C9") (pin "1") (pinfunction "1_1") (pintype "passive"))
      (node (ref "D1") (pin "K") (pinfunction "K_K") (pintype "passive"))
      (node (ref "Gnd") (pin "1") (pinfunction "TP_1") (pintype "passive"))
      (node (ref "J1") (pin "G") (pinfunction "USBGnd_G") (pintype "passive"))
      (node (ref "L2") (pin "2") (pinfunction "2_2") (pintype "passive"))
      (node (ref "P1") (pin "2") (pinfunction "Gnd_2") (pintype "passive"))
      (node (ref "P2") (pin "15") (pinfunction "Gnd_15") (pintype "passive"))
      (node (ref "P2") (pin "17") (pinfunction "Gnd_17") (pintype "passive"))
      (node (ref "P2") (pin "19") (pinfunction "Gnd_19") (pintype "passive"))
      (node (ref "P2") (pin "3") (pinfunction "Gnd_3") (pintype "passive"))
      (node (ref "P2") (pin "5") (pinfunction "Gnd_5") (pintype "passive"))
      (node (ref "P3") (pin "3") (pinfunction "Gnd_3") (pintype "passive"))
      (node (ref "P3") (pin "5") (pinfunction "Gnd_5") (pintype "passive"))
      (node (ref "P3") (pin "9") (pinfunction "GndDet_9") (pintype "passive"))
      (node (ref "R10") (pin "2") (pinfunction "2_2") (pintype "passive"))
      (node (ref "R13") (pin "1") (pinfunction "1_1") (pintype "passive"))
      (node (ref "R14") (pin "1") (pinfunction "1_1") (pintype "passive"))
      (node (ref "R16") (pin "2") (pinfunction "2_2") (pintype "passive"))
      (node (ref "R20") (pin "2") (pinfunction "2_2") (pintype "passive"))
      (node (ref "R21") (pin "1") (pinfunction "1_1") (pintype "passive"))
      (node (ref "R22") (pin "1") (pinfunction "1_1") (pintype "passive"))
      (node (ref "R3") (pin "2") (pinfunction "2_2") (pintype "passive"))
      (node (ref "S1") (pin "1") (pinfunction "1_1") (pintype "passive"))
      (node (ref "U1") (pin "2") (pinfunction "Gnd_2") (pintype "power_in"))
      (node (ref "U2") (pin "2") (pinfunction "GND_2") (pintype "power_in"))
      (node (ref "U3") (pin "1") (pinfunction "Gnd_1") (pintype "passive"))
      (node (ref "U4") (pin "4") (pinfunction "Gnd_4") (pintype "power_in"))
      (node (ref "U4") (pin "5") (pinfunction "DIR_5") (pintype "input"))
      (node (ref "U5") (pin "15") (pinfunction "VRefL_15") (pintype "passive"))
      (node (ref "U5") (pin "16") (pinfunction "VssA_16") (pintype "power_in"))
      (node (ref "U5") (pin "31") (pinfunction "Vss_31") (pintype "power_in"))
      (node (ref "U5") (pin "4") (pinfunction "Vss_4") (pintype "power_in"))
      (node (ref "U6") (pin "4") (pinfunction "Gnd_4") (pintype "power_in"))
      (node (ref "U7") (pin "2") (pinfunction "Gnd_2") (pintype "power_in"))
      (node (ref "Y1") (pin "2") (pinfunction "Gnd_2") (pintype "passive"))
      (node (ref "Y1") (pin "4") (pinfunction "Gnd_4") (pintype "passive"))
      (node (ref "Z1") (pin "2") (pintype "passive"))
    )
    (net (code "50") (name "Net-(D1-PadA)") (class "Default")
      (node (ref "D1") (pin "A") (pinfunction "A_A") (pintype "passive"))
      (node (ref "R7") (pin "1") (pinfunction "1_1") (pintype "passive"))
    )
    (net (code "51") (name "Net-(D2-PadK)") (class "Default")
      (node (ref "D2") (pin "K") (pinfunction "K_K") (pintype "passive"))
      (node (ref "R21") (pin "2") (pinfunction "2_2") (pintype "passive"))
    )
    (net (code "52") (name "Net-(J1-USB+5v)") (class "Default")
      (node (ref "J1") (pin "VBUS") (pinfunction "USB+5v_VBUS") (pintype "power_in"))
      (node (ref "L1") (pin "1") (pinfunction "1_1") (pintype "passive"))
    )
    (net (code "53") (name "Net-(J1-USBDM)") (class "Default")
      (node (ref "J1") (pin "D-") (pinfunction "USBDM_D-") (pintype "passive"))
      (node (ref "R2") (pin "1") (pinfunction "1_1") (pintype "passive"))
    )
    (net (code "54") (name "Net-(J1-USBDP)") (class "Default")
      (node (ref "J1") (pin "D+") (pinfunction "USBDP_D+") (pintype "passive"))
      (node (ref "R4") (pin "1") (pinfunction "1_1") (pintype "passive"))
    )
    (net (code "55") (name "Net-(U1-A)") (class "Default")
      (node (ref "R1") (pin "2") (pinfunction "2_2") (pintype "passive"))
      (node (ref "U1") (pin "3") (pinfunction "A_3") (pintype "bidirectional"))
    )
    (net (code "56") (name "Net-(U1-B)") (class "Default")
      (node (ref "R6") (pin "1") (pinfunction "1_1") (pintype "passive"))
      (node (ref "U1") (pin "4") (pinfunction "B_4") (pintype "bidirectional"))
      (node (ref "U4") (pin "7") (pinfunction "B1_7") (pintype "bidirectional"))
    )
    (net (code "57") (name "Net-(U4-B2)") (class "Default")
      (node (ref "R8") (pin "1") (pinfunction "1_1") (pintype "passive"))
      (node (ref "U4") (pin "6") (pinfunction "B2_6") (pintype "bidirectional"))
    )
    (net (code "58") (name "Net-(U6-B1)") (class "Default")
      (node (ref "R12") (pin "1") (pinfunction "1_1") (pintype "passive"))
      (node (ref "U6") (pin "7") (pinfunction "B1_7") (pintype "bidirectional"))
    )
    (net (code "59") (name "Net-(U6-B2)") (class "Default")
      (node (ref "R15") (pin "1") (pinfunction "1_1") (pintype "passive"))
      (node (ref "U6") (pin "6") (pinfunction "B2_6") (pintype "bidirectional"))
    )
    (net (code "60") (name "Net-(U7-A)") (class "Default")
      (node (ref "R19") (pin "2") (pinfunction "2_2") (pintype "passive"))
      (node (ref "U7") (pin "3") (pinfunction "A_3") (pintype "bidirectional"))
    )
    (net (code "61") (name "Net-(U7-B)") (class "Default")
      (node (ref "R18") (pin "1") (pinfunction "1_1") (pintype "passive"))
      (node (ref "U7") (pin "4") (pinfunction "B_4") (pintype "bidirectional"))
    )
    (net (code "62") (name "VDD_BDM") (class "Default")
      (node (ref "C1") (pin "2") (pinfunction "2_2") (pintype "passive"))
      (node (ref "C10") (pin "2") (pinfunction "2_2") (pintype "passive"))
      (node (ref "C12") (pin "2") (pinfunction "2_2") (pintype "passive"))
      (node (ref "JP1") (pin "2") (pinfunction "2_2") (pintype "passive"))
      (node (ref "P1") (pin "6") (pinfunction "TVdd_6") (pintype "passive"))
      (node (ref "P2") (pin "1") (pinfunction "VTref_1") (pintype "passive"))
      (node (ref "R17") (pin "1") (pinfunction "1_1") (pintype "passive"))
      (node (ref "R5") (pin "1") (pinfunction "1_1") (pintype "passive"))
      (node (ref "R9") (pin "2") (pinfunction "2_2") (pintype "passive"))
      (node (ref "U1") (pin "6") (pinfunction "VccB_6") (pintype "power_in"))
      (node (ref "U4") (pin "8") (pinfunction "VccB_8") (pintype "power_in"))
      (node (ref "U6") (pin "8") (pinfunction "VccB_8") (pintype "power_in"))
      (node (ref "U7") (pin "6") (pinfunction "VccB_6") (pintype "power_in"))
    )
    (net (code "63") (name "unconnected-(J1-USB_ID-PadID)") (class "Default")
      (node (ref "J1") (pin "ID") (pinfunction "USB_ID_ID") (pintype "passive"))
    )
    (net (code "64") (name "unconnected-(P2-GndDet-Pad9)") (class "Default")
      (node (ref "P2") (pin "9") (pinfunction "GndDet_9") (pintype "passive+no_connect"))
    )
    (net (code "65") (name "unconnected-(P2-T'DATA1-Pad16)") (class "Default")
      (node (ref "P2") (pin "16") (pinfunction "T'DATA1_16") (pintype "passive+no_connect"))
    )
    (net (code "66") (name "unconnected-(P2-T'DATA2-Pad18)") (class "Default")
      (node (ref "P2") (pin "18") (pinfunction "T'DATA2_18") (pintype "passive+no_connect"))
    )
    (net (code "67") (name "unconnected-(P2-T'DATA3-Pad20)") (class "Default")
      (node (ref "P2") (pin "20") (pinfunction "T'DATA3_20") (pintype "passive+no_connect"))
    )
    (net (code "68") (name "unconnected-(U2-CSLEW-Pad5)") (class "Default")
      (node (ref "U2") (pin "5") (pinfunction "CSLEW_5") (pintype "passive"))
    )
    (net (code "69") (name "unconnected-(U5-PTB18-Pad41)") (class "Default")
      (node (ref "U5") (pin "41") (pinfunction "PTB18_41") (pintype "bidirectional"))
    )
    (net (code "70") (name "unconnected-(U5-PTB19-Pad42)") (class "Default")
      (node (ref "U5") (pin "42") (pinfunction "PTB19_42") (pintype "bidirectional"))
    )
    (net (code "71") (name "unconnected-(U5-PTC8-Pad53)") (class "Default")
      (node (ref "U5") (pin "53") (pinfunction "PTC8_53") (pintype "bidirectional"))
    )
    (net (code "72") (name "unconnected-(U5-PTC9-Pad54)") (class "Default")
      (node (ref "U5") (pin "54") (pinfunction "PTC9_54") (pintype "bidirectional"))
    )
    (net (code "73") (name "unconnected-(U5-PTC10-Pad55)") (class "Default")
      (node (ref "U5") (pin "55") (pinfunction "PTC10_55") (pintype "bidirectional"))
    )
    (net (code "74") (name "unconnected-(U5-PTC11{slash}LLWU_P11-Pad56)") (class "Default")
      (node (ref "U5") (pin "56") (pinfunction "PTC11/LLWU_P11_56") (pintype "bidirectional"))
    )
    (net (code "75") (name "unconnected-(U5-PTE0{slash}CLKOUT32K-Pad1)") (class "Default")
      (node (ref "U5") (pin "1") (pinfunction "PTE0/CLKOUT32K_1") (pintype "bidirectional"))
    )
    (net (code "76") (name "unconnected-(U5-PTE1{slash}LLWU_P0-Pad2)") (class "Default")
      (node (ref "U5") (pin "2") (pinfunction "PTE1/LLWU_P0_2") (pintype "bidirectional"))
    )
    (net (code "77") (name "unconnected-(U5-Vdd-Pad48)") (class "Default")
      (node (ref "U5") (pin "48") (pinfunction "Vdd_48") (pintype "power_in"))
    )
    (net (code "78") (name "unconnected-(U5-Vss-Pad47)") (class "Default")
      (node (ref "U5") (pin "47") (pinfunction "Vss_47") (pintype "power_in"))
    )
  )
)
